# old_control_board.net
KiCad netlist of a schematic drawn in EAGLE
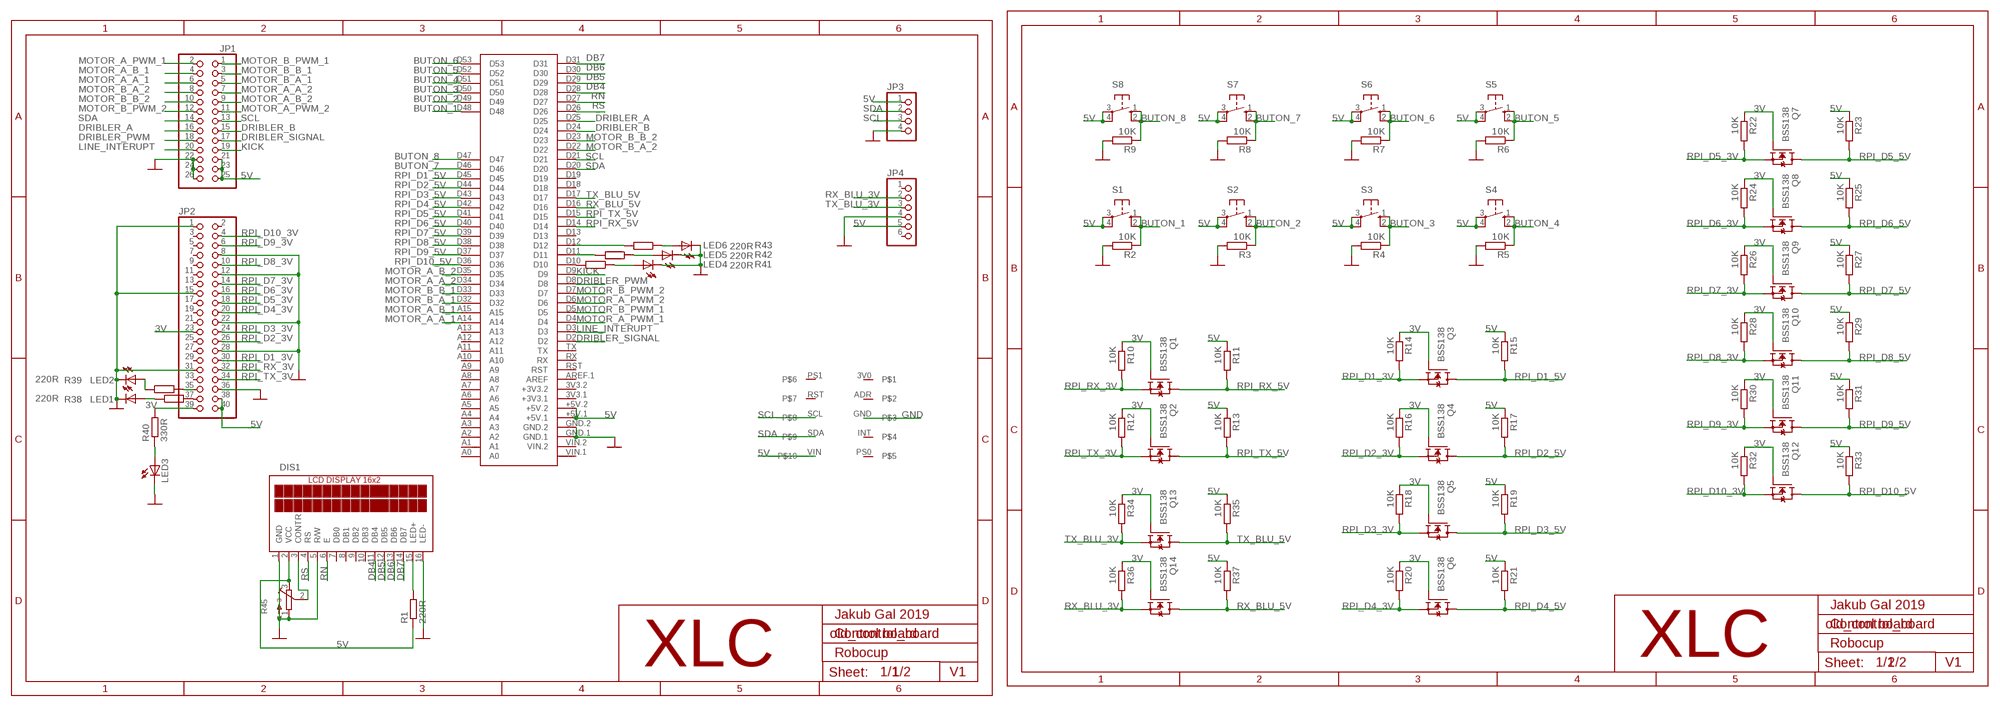
[diagram p0: schematic, sheet 1]

(export (version "E")
  (design (tool "Eeschema 10.0.6"))
  (components
    (comp (ref "DIS1")
      (value "LCD_DISPLEJ_16X2Z")
      (footprint "eagle-import:LCD_DISPLEJ_16X2")
      (libsource (lib "eagle-import") (part "LCD_DISPLEJ_16X2Z"))
    )
    (comp (ref "JP1")
      (value "PINHD-2X13_2.54")
      (footprint "eagle-import:2X13")
      (libsource (lib "eagle-import") (part "PINHD-2X13_2.54"))
    )
    (comp (ref "JP2")
      (value "PINHD-2X20_2.54")
      (footprint "eagle-import:2X20")
      (libsource (lib "eagle-import") (part "PINHD-2X20_2.54"))
    )
    (comp (ref "JP3")
      (value "PINHD-1X4_2.54")
      (footprint "eagle-import:1X04")
      (libsource (lib "eagle-import") (part "PINHD-1X4_2.54"))
    )
    (comp (ref "JP4")
      (value "PINHD-1X6_2.54")
      (footprint "eagle-import:1X06")
      (libsource (lib "eagle-import") (part "PINHD-1X6_2.54"))
    )
    (comp (ref "LED1")
      (value "LEDCHIPLED_0603")
      (footprint "eagle-import:CHIPLED_0603")
      (libsource (lib "eagle-import") (part "LEDCHIPLED_0603"))
    )
    (comp (ref "LED2")
      (value "LEDCHIPLED_0603")
      (footprint "eagle-import:CHIPLED_0603")
      (libsource (lib "eagle-import") (part "LEDCHIPLED_0603"))
    )
    (comp (ref "LED3")
      (value "LEDCHIPLED_0603")
      (footprint "eagle-import:CHIPLED_0603")
      (libsource (lib "eagle-import") (part "LEDCHIPLED_0603"))
    )
    (comp (ref "LED4")
      (value "LEDCHIPLED_0603")
      (footprint "eagle-import:CHIPLED_0603")
      (libsource (lib "eagle-import") (part "LEDCHIPLED_0603"))
    )
    (comp (ref "LED5")
      (value "LEDCHIPLED_0603")
      (footprint "eagle-import:CHIPLED_0603")
      (libsource (lib "eagle-import") (part "LEDCHIPLED_0603"))
    )
    (comp (ref "LED6")
      (value "LEDCHIPLED_0603")
      (footprint "eagle-import:CHIPLED_0603")
      (libsource (lib "eagle-import") (part "LEDCHIPLED_0603"))
    )
    (comp (ref "Q1")
      (value "BSS138")
      (footprint "eagle-import:SOT23")
      (fields (field (name "MF") "Fairchild"))
      (libsource (lib "eagle-import") (part "BSS138"))
    )
    (comp (ref "Q2")
      (value "BSS138")
      (footprint "eagle-import:SOT23")
      (fields (field (name "MF") "Fairchild"))
      (libsource (lib "eagle-import") (part "BSS138"))
    )
    (comp (ref "Q3")
      (value "BSS138")
      (footprint "eagle-import:SOT23")
      (fields (field (name "MF") "Fairchild"))
      (libsource (lib "eagle-import") (part "BSS138"))
    )
    (comp (ref "Q4")
      (value "BSS138")
      (footprint "eagle-import:SOT23")
      (fields (field (name "MF") "Fairchild"))
      (libsource (lib "eagle-import") (part "BSS138"))
    )
    (comp (ref "Q5")
      (value "BSS138")
      (footprint "eagle-import:SOT23")
      (fields (field (name "MF") "Fairchild"))
      (libsource (lib "eagle-import") (part "BSS138"))
    )
    (comp (ref "Q6")
      (value "BSS138")
      (footprint "eagle-import:SOT23")
      (fields (field (name "MF") "Fairchild"))
      (libsource (lib "eagle-import") (part "BSS138"))
    )
    (comp (ref "Q7")
      (value "BSS138")
      (footprint "eagle-import:SOT23")
      (fields (field (name "MF") "Fairchild"))
      (libsource (lib "eagle-import") (part "BSS138"))
    )
    (comp (ref "Q8")
      (value "BSS138")
      (footprint "eagle-import:SOT23")
      (fields (field (name "MF") "Fairchild"))
      (libsource (lib "eagle-import") (part "BSS138"))
    )
    (comp (ref "Q9")
      (value "BSS138")
      (footprint "eagle-import:SOT23")
      (fields (field (name "MF") "Fairchild"))
      (libsource (lib "eagle-import") (part "BSS138"))
    )
    (comp (ref "Q10")
      (value "BSS138")
      (footprint "eagle-import:SOT23")
      (fields (field (name "MF") "Fairchild"))
      (libsource (lib "eagle-import") (part "BSS138"))
    )
    (comp (ref "Q11")
      (value "BSS138")
      (footprint "eagle-import:SOT23")
      (fields (field (name "MF") "Fairchild"))
      (libsource (lib "eagle-import") (part "BSS138"))
    )
    (comp (ref "Q12")
      (value "BSS138")
      (footprint "eagle-import:SOT23")
      (fields (field (name "MF") "Fairchild"))
      (libsource (lib "eagle-import") (part "BSS138"))
    )
    (comp (ref "Q13")
      (value "BSS138")
      (footprint "eagle-import:SOT23")
      (fields (field (name "MF") "Fairchild"))
      (libsource (lib "eagle-import") (part "BSS138"))
    )
    (comp (ref "Q14")
      (value "BSS138")
      (footprint "eagle-import:SOT23")
      (fields (field (name "MF") "Fairchild"))
      (libsource (lib "eagle-import") (part "BSS138"))
    )
    (comp (ref "R1")
      (value "220R")
      (footprint "eagle-import:R0603")
      (libsource (lib "eagle-import") (part "R-EU_R0603"))
    )
    (comp (ref "R2")
      (value "10K")
      (footprint "eagle-import:R0603")
      (libsource (lib "eagle-import") (part "R-EU_R0603"))
    )
    (comp (ref "R3")
      (value "10K")
      (footprint "eagle-import:R0603")
      (libsource (lib "eagle-import") (part "R-EU_R0603"))
    )
    (comp (ref "R4")
      (value "10K")
      (footprint "eagle-import:R0603")
      (libsource (lib "eagle-import") (part "R-EU_R0603"))
    )
    (comp (ref "R5")
      (value "10K")
      (footprint "eagle-import:R0603")
      (libsource (lib "eagle-import") (part "R-EU_R0603"))
    )
    (comp (ref "R6")
      (value "10K")
      (footprint "eagle-import:R0603")
      (libsource (lib "eagle-import") (part "R-EU_R0603"))
    )
    (comp (ref "R7")
      (value "10K")
      (footprint "eagle-import:R0603")
      (libsource (lib "eagle-import") (part "R-EU_R0603"))
    )
    (comp (ref "R8")
      (value "10K")
      (footprint "eagle-import:R0603")
      (libsource (lib "eagle-import") (part "R-EU_R0603"))
    )
    (comp (ref "R9")
      (value "10K")
      (footprint "eagle-import:R0603")
      (libsource (lib "eagle-import") (part "R-EU_R0603"))
    )
    (comp (ref "R10")
      (value "10K")
      (footprint "eagle-import:R0603")
      (libsource (lib "eagle-import") (part "R-EU_R0603"))
    )
    (comp (ref "R11")
      (value "10K")
      (footprint "eagle-import:R0603")
      (libsource (lib "eagle-import") (part "R-EU_R0603"))
    )
    (comp (ref "R12")
      (value "10K")
      (footprint "eagle-import:R0603")
      (libsource (lib "eagle-import") (part "R-EU_R0603"))
    )
    (comp (ref "R13")
      (value "10K")
      (footprint "eagle-import:R0603")
      (libsource (lib "eagle-import") (part "R-EU_R0603"))
    )
    (comp (ref "R14")
      (value "10K")
      (footprint "eagle-import:R0603")
      (libsource (lib "eagle-import") (part "R-EU_R0603"))
    )
    (comp (ref "R15")
      (value "10K")
      (footprint "eagle-import:R0603")
      (libsource (lib "eagle-import") (part "R-EU_R0603"))
    )
    (comp (ref "R16")
      (value "10K")
      (footprint "eagle-import:R0603")
      (libsource (lib "eagle-import") (part "R-EU_R0603"))
    )
    (comp (ref "R17")
      (value "10K")
      (footprint "eagle-import:R0603")
      (libsource (lib "eagle-import") (part "R-EU_R0603"))
    )
    (comp (ref "R18")
      (value "10K")
      (footprint "eagle-import:R0603")
      (libsource (lib "eagle-import") (part "R-EU_R0603"))
    )
    (comp (ref "R19")
      (value "10K")
      (footprint "eagle-import:R0603")
      (libsource (lib "eagle-import") (part "R-EU_R0603"))
    )
    (comp (ref "R20")
      (value "10K")
      (footprint "eagle-import:R0603")
      (libsource (lib "eagle-import") (part "R-EU_R0603"))
    )
    (comp (ref "R21")
      (value "10K")
      (footprint "eagle-import:R0603")
      (libsource (lib "eagle-import") (part "R-EU_R0603"))
    )
    (comp (ref "R22")
      (value "10K")
      (footprint "eagle-import:R0603")
      (libsource (lib "eagle-import") (part "R-EU_R0603"))
    )
    (comp (ref "R23")
      (value "10K")
      (footprint "eagle-import:R0603")
      (libsource (lib "eagle-import") (part "R-EU_R0603"))
    )
    (comp (ref "R24")
      (value "10K")
      (footprint "eagle-import:R0603")
      (libsource (lib "eagle-import") (part "R-EU_R0603"))
    )
    (comp (ref "R25")
      (value "10K")
      (footprint "eagle-import:R0603")
      (libsource (lib "eagle-import") (part "R-EU_R0603"))
    )
    (comp (ref "R26")
      (value "10K")
      (footprint "eagle-import:R0603")
      (libsource (lib "eagle-import") (part "R-EU_R0603"))
    )
    (comp (ref "R27")
      (value "10K")
      (footprint "eagle-import:R0603")
      (libsource (lib "eagle-import") (part "R-EU_R0603"))
    )
    (comp (ref "R28")
      (value "10K")
      (footprint "eagle-import:R0603")
      (libsource (lib "eagle-import") (part "R-EU_R0603"))
    )
    (comp (ref "R29")
      (value "10K")
      (footprint "eagle-import:R0603")
      (libsource (lib "eagle-import") (part "R-EU_R0603"))
    )
    (comp (ref "R30")
      (value "10K")
      (footprint "eagle-import:R0603")
      (libsource (lib "eagle-import") (part "R-EU_R0603"))
    )
    (comp (ref "R31")
      (value "10K")
      (footprint "eagle-import:R0603")
      (libsource (lib "eagle-import") (part "R-EU_R0603"))
    )
    (comp (ref "R32")
      (value "10K")
      (footprint "eagle-import:R0603")
      (libsource (lib "eagle-import") (part "R-EU_R0603"))
    )
    (comp (ref "R33")
      (value "10K")
      (footprint "eagle-import:R0603")
      (libsource (lib "eagle-import") (part "R-EU_R0603"))
    )
    (comp (ref "R34")
      (value "10K")
      (footprint "eagle-import:R0603")
      (libsource (lib "eagle-import") (part "R-EU_R0603"))
    )
    (comp (ref "R35")
      (value "10K")
      (footprint "eagle-import:R0603")
      (libsource (lib "eagle-import") (part "R-EU_R0603"))
    )
    (comp (ref "R36")
      (value "10K")
      (footprint "eagle-import:R0603")
      (libsource (lib "eagle-import") (part "R-EU_R0603"))
    )
    (comp (ref "R37")
      (value "10K")
      (footprint "eagle-import:R0603")
      (libsource (lib "eagle-import") (part "R-EU_R0603"))
    )
    (comp (ref "R38")
      (value "220R")
      (footprint "eagle-import:R0603")
      (libsource (lib "eagle-import") (part "R-EU_R0603"))
    )
    (comp (ref "R39")
      (value "220R")
      (footprint "eagle-import:R0603")
      (libsource (lib "eagle-import") (part "R-EU_R0603"))
    )
    (comp (ref "R40")
      (value "330R")
      (footprint "eagle-import:R0603")
      (libsource (lib "eagle-import") (part "R-EU_R0603"))
    )
    (comp (ref "R41")
      (value "220R")
      (footprint "eagle-import:R0603")
      (libsource (lib "eagle-import") (part "R-EU_R0603"))
    )
    (comp (ref "R42")
      (value "220R")
      (footprint "eagle-import:R0603")
      (libsource (lib "eagle-import") (part "R-EU_R0603"))
    )
    (comp (ref "R43")
      (value "220R")
      (footprint "eagle-import:R0603")
      (libsource (lib "eagle-import") (part "R-EU_R0603"))
    )
    (comp (ref "R45")
      (value "3362P")
      (footprint "eagle-import:3362P")
      (libsource (lib "eagle-import") (part "3362P"))
    )
    (comp (ref "S1")
      (value "10-XX")
      (footprint "eagle-import:B3F-10XX")
      (fields (field (name "MPN") "B3F-1000"))
      (libsource (lib "eagle-import") (part "10-XX"))
    )
    (comp (ref "S2")
      (value "10-XX")
      (footprint "eagle-import:B3F-10XX")
      (fields (field (name "MPN") "B3F-1000"))
      (libsource (lib "eagle-import") (part "10-XX"))
    )
    (comp (ref "S3")
      (value "10-XX")
      (footprint "eagle-import:B3F-10XX")
      (fields (field (name "MPN") "B3F-1000"))
      (libsource (lib "eagle-import") (part "10-XX"))
    )
    (comp (ref "S4")
      (value "10-XX")
      (footprint "eagle-import:B3F-10XX")
      (fields (field (name "MPN") "B3F-1000"))
      (libsource (lib "eagle-import") (part "10-XX"))
    )
    (comp (ref "S5")
      (value "10-XX")
      (footprint "eagle-import:B3F-10XX")
      (fields (field (name "MPN") "B3F-1000"))
      (libsource (lib "eagle-import") (part "10-XX"))
    )
    (comp (ref "S6")
      (value "10-XX")
      (footprint "eagle-import:B3F-10XX")
      (fields (field (name "MPN") "B3F-1000"))
      (libsource (lib "eagle-import") (part "10-XX"))
    )
    (comp (ref "S7")
      (value "10-XX")
      (footprint "eagle-import:B3F-10XX")
      (fields (field (name "MPN") "B3F-1000"))
      (libsource (lib "eagle-import") (part "10-XX"))
    )
    (comp (ref "S8")
      (value "10-XX")
      (footprint "eagle-import:B3F-10XX")
      (fields (field (name "MPN") "B3F-1000"))
      (libsource (lib "eagle-import") (part "10-XX"))
    )
    (comp (ref "U$1")
      (value "MEGA2560_MIKRO")
      (footprint "eagle-import:MEGA2560_MIKRO")
      (libsource (lib "eagle-import") (part "MEGA2560_MIKRO"))
    )
    (comp (ref "U$2")
      (value "BNO055")
      (footprint "eagle-import:BNO005")
      (libsource (lib "eagle-import") (part "BNO055"))
    )
  )
  (nets
    (net (code "1") (name "/3V") (class "Default")
      (node (ref "JP2") (pin "23") (pinfunction "23_23") (pintype "passive"))
      (node (ref "JP2") (pin "39") (pinfunction "39_39") (pintype "passive"))
      (node (ref "Q1") (pin "1") (pinfunction "G_1") (pintype "passive"))
      (node (ref "Q10") (pin "1") (pinfunction "G_1") (pintype "passive"))
      (node (ref "Q11") (pin "1") (pinfunction "G_1") (pintype "passive"))
      (node (ref "Q12") (pin "1") (pinfunction "G_1") (pintype "passive"))
      (node (ref "Q13") (pin "1") (pinfunction "G_1") (pintype "passive"))
      (node (ref "Q14") (pin "1") (pinfunction "G_1") (pintype "passive"))
      (node (ref "Q2") (pin "1") (pinfunction "G_1") (pintype "passive"))
      (node (ref "Q3") (pin "1") (pinfunction "G_1") (pintype "passive"))
      (node (ref "Q4") (pin "1") (pinfunction "G_1") (pintype "passive"))
      (node (ref "Q5") (pin "1") (pinfunction "G_1") (pintype "passive"))
      (node (ref "Q6") (pin "1") (pinfunction "G_1") (pintype "passive"))
      (node (ref "Q7") (pin "1") (pinfunction "G_1") (pintype "passive"))
      (node (ref "Q8") (pin "1") (pinfunction "G_1") (pintype "passive"))
      (node (ref "Q9") (pin "1") (pinfunction "G_1") (pintype "passive"))
      (node (ref "R10") (pin "1") (pinfunction "1_1") (pintype "passive"))
      (node (ref "R12") (pin "1") (pinfunction "1_1") (pintype "passive"))
      (node (ref "R14") (pin "1") (pinfunction "1_1") (pintype "passive"))
      (node (ref "R16") (pin "1") (pinfunction "1_1") (pintype "passive"))
      (node (ref "R18") (pin "1") (pinfunction "1_1") (pintype "passive"))
      (node (ref "R20") (pin "1") (pinfunction "1_1") (pintype "passive"))
      (node (ref "R22") (pin "1") (pinfunction "1_1") (pintype "passive"))
      (node (ref "R24") (pin "1") (pinfunction "1_1") (pintype "passive"))
      (node (ref "R26") (pin "1") (pinfunction "1_1") (pintype "passive"))
      (node (ref "R28") (pin "1") (pinfunction "1_1") (pintype "passive"))
      (node (ref "R30") (pin "1") (pinfunction "1_1") (pintype "passive"))
      (node (ref "R32") (pin "1") (pinfunction "1_1") (pintype "passive"))
      (node (ref "R34") (pin "1") (pinfunction "1_1") (pintype "passive"))
      (node (ref "R36") (pin "1") (pinfunction "1_1") (pintype "passive"))
      (node (ref "R40") (pin "2") (pinfunction "2_2") (pintype "passive"))
    )
    (net (code "2") (name "/5V") (class "Default")
      (node (ref "DIS1") (pin "2") (pinfunction "VCC_2") (pintype "power_in"))
      (node (ref "JP1") (pin "21") (pinfunction "21_21") (pintype "passive"))
      (node (ref "JP1") (pin "23") (pinfunction "23_23") (pintype "passive"))
      (node (ref "JP1") (pin "25") (pinfunction "25_25") (pintype "passive"))
      (node (ref "JP2") (pin "38") (pinfunction "38_38") (pintype "passive"))
      (node (ref "JP2") (pin "40") (pinfunction "40_40") (pintype "passive"))
      (node (ref "JP3") (pin "1") (pinfunction "1_1") (pintype "passive"))
      (node (ref "JP4") (pin "5") (pinfunction "5_5") (pintype "passive"))
      (node (ref "R1") (pin "1") (pinfunction "1_1") (pintype "passive"))
      (node (ref "R11") (pin "1") (pinfunction "1_1") (pintype "passive"))
      (node (ref "R13") (pin "1") (pinfunction "1_1") (pintype "passive"))
      (node (ref "R15") (pin "1") (pinfunction "1_1") (pintype "passive"))
      (node (ref "R17") (pin "1") (pinfunction "1_1") (pintype "passive"))
      (node (ref "R19") (pin "1") (pinfunction "1_1") (pintype "passive"))
      (node (ref "R21") (pin "1") (pinfunction "1_1") (pintype "passive"))
      (node (ref "R23") (pin "1") (pinfunction "1_1") (pintype "passive"))
      (node (ref "R25") (pin "1") (pinfunction "1_1") (pintype "passive"))
      (node (ref "R27") (pin "1") (pinfunction "1_1") (pintype "passive"))
      (node (ref "R29") (pin "1") (pinfunction "1_1") (pintype "passive"))
      (node (ref "R31") (pin "1") (pinfunction "1_1") (pintype "passive"))
      (node (ref "R33") (pin "1") (pinfunction "1_1") (pintype "passive"))
      (node (ref "R35") (pin "1") (pinfunction "1_1") (pintype "passive"))
      (node (ref "R37") (pin "1") (pinfunction "1_1") (pintype "passive"))
      (node (ref "R45") (pin "3") (pinfunction "3_3") (pintype "passive"))
      (node (ref "S1") (pin "3") (pinfunction "P_3") (pintype "passive"))
      (node (ref "S1") (pin "4") (pinfunction "P1_4") (pintype "passive"))
      (node (ref "S2") (pin "3") (pinfunction "P_3") (pintype "passive"))
      (node (ref "S2") (pin "4") (pinfunction "P1_4") (pintype "passive"))
      (node (ref "S3") (pin "3") (pinfunction "P_3") (pintype "passive"))
      (node (ref "S3") (pin "4") (pinfunction "P1_4") (pintype "passive"))
      (node (ref "S4") (pin "3") (pinfunction "P_3") (pintype "passive"))
      (node (ref "S4") (pin "4") (pinfunction "P1_4") (pintype "passive"))
      (node (ref "S5") (pin "3") (pinfunction "P_3") (pintype "passive"))
      (node (ref "S5") (pin "4") (pinfunction "P1_4") (pintype "passive"))
      (node (ref "S6") (pin "3") (pinfunction "P_3") (pintype "passive"))
      (node (ref "S6") (pin "4") (pinfunction "P1_4") (pintype "passive"))
      (node (ref "S7") (pin "3") (pinfunction "P_3") (pintype "passive"))
      (node (ref "S7") (pin "4") (pinfunction "P1_4") (pintype "passive"))
      (node (ref "S8") (pin "3") (pinfunction "P_3") (pintype "passive"))
      (node (ref "S8") (pin "4") (pinfunction "P1_4") (pintype "passive"))
      (node (ref "U$1") (pin "+5V.1") (pinfunction "+5V.1_+5V.1") (pintype "bidirectional"))
      (node (ref "U$1") (pin "+5V.2") (pinfunction "+5V.2_+5V.2") (pintype "bidirectional"))
      (node (ref "U$2") (pin "VIN") (pinfunction "P$10_VIN") (pintype "bidirectional"))
    )
    (net (code "3") (name "/BUTON_1") (class "Default")
      (node (ref "R2") (pin "1") (pinfunction "1_1") (pintype "passive"))
      (node (ref "S1") (pin "1") (pinfunction "S_1") (pintype "passive"))
      (node (ref "S1") (pin "2") (pinfunction "S1_2") (pintype "passive"))
      (node (ref "U$1") (pin "D48") (pinfunction "D48_D48") (pintype "bidirectional"))
    )
    (net (code "4") (name "/BUTON_2") (class "Default")
      (node (ref "R3") (pin "1") (pinfunction "1_1") (pintype "passive"))
      (node (ref "S2") (pin "1") (pinfunction "S_1") (pintype "passive"))
      (node (ref "S2") (pin "2") (pinfunction "S1_2") (pintype "passive"))
      (node (ref "U$1") (pin "D49") (pinfunction "D49_D49") (pintype "bidirectional"))
    )
    (net (code "5") (name "/BUTON_3") (class "Default")
      (node (ref "R4") (pin "1") (pinfunction "1_1") (pintype "passive"))
      (node (ref "S3") (pin "1") (pinfunction "S_1") (pintype "passive"))
      (node (ref "S3") (pin "2") (pinfunction "S1_2") (pintype "passive"))
      (node (ref "U$1") (pin "D50") (pinfunction "D50_D50") (pintype "bidirectional"))
    )
    (net (code "6") (name "/BUTON_4") (class "Default")
      (node (ref "R5") (pin "1") (pinfunction "1_1") (pintype "passive"))
      (node (ref "S4") (pin "1") (pinfunction "S_1") (pintype "passive"))
      (node (ref "S4") (pin "2") (pinfunction "S1_2") (pintype "passive"))
      (node (ref "U$1") (pin "D51") (pinfunction "D51_D51") (pintype "bidirectional"))
    )
    (net (code "7") (name "/BUTON_5") (class "Default")
      (node (ref "R6") (pin "1") (pinfunction "1_1") (pintype "passive"))
      (node (ref "S5") (pin "1") (pinfunction "S_1") (pintype "passive"))
      (node (ref "S5") (pin "2") (pinfunction "S1_2") (pintype "passive"))
      (node (ref "U$1") (pin "D52") (pinfunction "D52_D52") (pintype "bidirectional"))
    )
    (net (code "8") (name "/BUTON_6") (class "Default")
      (node (ref "R7") (pin "1") (pinfunction "1_1") (pintype "passive"))
      (node (ref "S6") (pin "1") (pinfunction "S_1") (pintype "passive"))
      (node (ref "S6") (pin "2") (pinfunction "S1_2") (pintype "passive"))
      (node (ref "U$1") (pin "D53") (pinfunction "D53_D53") (pintype "bidirectional"))
    )
    (net (code "9") (name "/BUTON_7") (class "Default")
      (node (ref "R8") (pin "1") (pinfunction "1_1") (pintype "passive"))
      (node (ref "S7") (pin "1") (pinfunction "S_1") (pintype "passive"))
      (node (ref "S7") (pin "2") (pinfunction "S1_2") (pintype "passive"))
      (node (ref "U$1") (pin "D46") (pinfunction "D46_D46") (pintype "bidirectional"))
    )
    (net (code "10") (name "/BUTON_8") (class "Default")
      (node (ref "R9") (pin "1") (pinfunction "1_1") (pintype "passive"))
      (node (ref "S8") (pin "1") (pinfunction "S_1") (pintype "passive"))
      (node (ref "S8") (pin "2") (pinfunction "S1_2") (pintype "passive"))
      (node (ref "U$1") (pin "D47") (pinfunction "D47_D47") (pintype "bidirectional"))
    )
    (net (code "11") (name "/DB4") (class "Default")
      (node (ref "DIS1") (pin "11") (pinfunction "DB4_11") (pintype "bidirectional"))
      (node (ref "U$1") (pin "D28") (pinfunction "D28_D28") (pintype "bidirectional"))
    )
    (net (code "12") (name "/DB5") (class "Default")
      (node (ref "DIS1") (pin "12") (pinfunction "DB5_12") (pintype "bidirectional"))
      (node (ref "U$1") (pin "D29") (pinfunction "D29_D29") (pintype "bidirectional"))
    )
    (net (code "13") (name "/DB6") (class "Default")
      (node (ref "DIS1") (pin "13") (pinfunction "DB6_13") (pintype "bidirectional"))
      (node (ref "U$1") (pin "D30") (pinfunction "D30_D30") (pintype "bidirectional"))
    )
    (net (code "14") (name "/DB7") (class "Default")
      (node (ref "DIS1") (pin "14") (pinfunction "DB7_14") (pintype "bidirectional"))
      (node (ref "U$1") (pin "D31") (pinfunction "D31_D31") (pintype "bidirectional"))
    )
    (net (code "15") (name "/DRIBLER_A") (class "Default")
      (node (ref "JP1") (pin "16") (pinfunction "16_16") (pintype "passive"))
      (node (ref "U$1") (pin "D25") (pinfunction "D25_D25") (pintype "bidirectional"))
    )
    (net (code "16") (name "/DRIBLER_B") (class "Default")
      (node (ref "JP1") (pin "15") (pinfunction "15_15") (pintype "passive"))
      (node (ref "U$1") (pin "D24") (pinfunction "D24_D24") (pintype "bidirectional"))
    )
    (net (code "17") (name "/DRIBLER_PWM") (class "Default")
      (node (ref "JP1") (pin "18") (pinfunction "18_18") (pintype "passive"))
      (node (ref "U$1") (pin "D8") (pinfunction "D8_D8") (pintype "bidirectional"))
    )
    (net (code "18") (name "/DRIBLER_SIGNAL") (class "Default")
      (node (ref "JP1") (pin "17") (pinfunction "17_17") (pintype "passive"))
      (node (ref "U$1") (pin "D2") (pinfunction "D2_D2") (pintype "bidirectional"))
    )
    (net (code "19") (name "/KICK") (class "Default")
      (node (ref "JP1") (pin "19") (pinfunction "19_19") (pintype "passive"))
      (node (ref "U$1") (pin "D9") (pinfunction "D9_D9") (pintype "bidirectional"))
    )
    (net (code "20") (name "/LINE_INTERUPT") (class "Default")
      (node (ref "JP1") (pin "20") (pinfunction "20_20") (pintype "passive"))
      (node (ref "U$1") (pin "D3") (pinfunction "D3_D3") (pintype "bidirectional"))
    )
    (net (code "21") (name "/MOTOR_A_A_1") (class "Default")
      (node (ref "JP1") (pin "6") (pinfunction "6_6") (pintype "passive"))
      (node (ref "U$1") (pin "A14") (pinfunction "A14_A14") (pintype "bidirectional"))
    )
    (net (code "22") (name "/MOTOR_A_A_2") (class "Default")
      (node (ref "JP1") (pin "7") (pinfunction "7_7") (pintype "passive"))
      (node (ref "U$1") (pin "D34") (pinfunction "D34_D34") (pintype "bidirectional"))
    )
    (net (code "23") (name "/MOTOR_A_B_1") (class "Default")
      (node (ref "JP1") (pin "4") (pinfunction "4_4") (pintype "passive"))
      (node (ref "U$1") (pin "A15") (pinfunction "A15_A15") (pintype "bidirectional"))
    )
    (net (code "24") (name "/MOTOR_A_B_2") (class "Default")
      (node (ref "JP1") (pin "9") (pinfunction "9_9") (pintype "passive"))
      (node (ref "U$1") (pin "D35") (pinfunction "D35_D35") (pintype "bidirectional"))
    )
    (net (code "25") (name "/MOTOR_A_PWM_1") (class "Default")
      (node (ref "JP1") (pin "2") (pinfunction "2_2") (pintype "passive"))
      (node (ref "U$1") (pin "D4") (pinfunction "D4_D4") (pintype "bidirectional"))
    )
    (net (code "26") (name "/MOTOR_A_PWM_2") (class "Default")
      (node (ref "JP1") (pin "11") (pinfunction "11_11") (pintype "passive"))
      (node (ref "U$1") (pin "D6") (pinfunction "D6_D6") (pintype "bidirectional"))
    )
    (net (code "27") (name "/MOTOR_B_A_1") (class "Default")
      (node (ref "JP1") (pin "5") (pinfunction "5_5") (pintype "passive"))
      (node (ref "U$1") (pin "D32") (pinfunction "D32_D32") (pintype "bidirectional"))
    )
    (net (code "28") (name "/MOTOR_B_A_2") (class "Default")
      (node (ref "JP1") (pin "8") (pinfunction "8_8") (pintype "passive"))
      (node (ref "U$1") (pin "D22") (pinfunction "D22_D22") (pintype "bidirectional"))
    )
    (net (code "29") (name "/MOTOR_B_B_1") (class "Default")
      (node (ref "JP1") (pin "3") (pinfunction "3_3") (pintype "passive"))
      (node (ref "U$1") (pin "D33") (pinfunction "D33_D33") (pintype "bidirectional"))
    )
    (net (code "30") (name "/MOTOR_B_B_2") (class "Default")
      (node (ref "JP1") (pin "10") (pinfunction "10_10") (pintype "passive"))
      (node (ref "U$1") (pin "D23") (pinfunction "D23_D23") (pintype "bidirectional"))
    )
    (net (code "31") (name "/MOTOR_B_PWM_1") (class "Default")
      (node (ref "JP1") (pin "1") (pinfunction "1_1") (pintype "passive"))
      (node (ref "U$1") (pin "D5") (pinfunction "D5_D5") (pintype "bidirectional"))
    )
    (net (code "32") (name "/MOTOR_B_PWM_2") (class "Default")
      (node (ref "JP1") (pin "12") (pinfunction "12_12") (pintype "passive"))
      (node (ref "U$1") (pin "D7") (pinfunction "D7_D7") (pintype "bidirectional"))
    )
    (net (code "33") (name "/RN") (class "Default")
      (node (ref "DIS1") (pin "6") (pinfunction "E_6") (pintype "input"))
      (node (ref "U$1") (pin "D27") (pinfunction "D27_D27") (pintype "bidirectional"))
    )
    (net (code "34") (name "/RPI_D1_3V") (class "Default")
      (node (ref "JP2") (pin "30") (pinfunction "30_30") (pintype "passive"))
      (node (ref "Q3") (pin "2") (pinfunction "S_2") (pintype "passive"))
      (node (ref "R14") (pin "2") (pinfunction "2_2") (pintype "passive"))
    )
    (net (code "35") (name "/RPI_D1_5V") (class "Default")
      (node (ref "Q3") (pin "3") (pinfunction "D_3") (pintype "passive"))
      (node (ref "R15") (pin "2") (pinfunction "2_2") (pintype "passive"))
      (node (ref "U$1") (pin "D45") (pinfunction "D45_D45") (pintype "bidirectional"))
    )
    (net (code "36") (name "/RPI_D2_3V") (class "Default")
      (node (ref "JP2") (pin "26") (pinfunction "26_26") (pintype "passive"))
      (node (ref "Q4") (pin "2") (pinfunction "S_2") (pintype "passive"))
      (node (ref "R16") (pin "2") (pinfunction "2_2") (pintype "passive"))
    )
    (net (code "37") (name "/RPI_D2_5V") (class "Default")
      (node (ref "Q4") (pin "3") (pinfunction "D_3") (pintype "passive"))
      (node (ref "R17") (pin "2") (pinfunction "2_2") (pintype "passive"))
      (node (ref "U$1") (pin "D44") (pinfunction "D44_D44") (pintype "bidirectional"))
    )
    (net (code "38") (name "/RPI_D3_3V") (class "Default")
      (node (ref "JP2") (pin "24") (pinfunction "24_24") (pintype "passive"))
      (node (ref "Q5") (pin "2") (pinfunction "S_2") (pintype "passive"))
      (node (ref "R18") (pin "2") (pinfunction "2_2") (pintype "passive"))
    )
    (net (code "39") (name "/RPI_D3_5V") (class "Default")
      (node (ref "Q5") (pin "3") (pinfunction "D_3") (pintype "passive"))
      (node (ref "R19") (pin "2") (pinfunction "2_2") (pintype "passive"))
      (node (ref "U$1") (pin "D43") (pinfunction "D43_D43") (pintype "bidirectional"))
    )
    (net (code "40") (name "/RPI_D4_3V") (class "Default")
      (node (ref "JP2") (pin "20") (pinfunction "20_20") (pintype "passive"))
      (node (ref "Q6") (pin "2") (pinfunction "S_2") (pintype "passive"))
      (node (ref "R20") (pin "2") (pinfunction "2_2") (pintype "passive"))
    )
    (net (code "41") (name "/RPI_D4_5V") (class "Default")
      (node (ref "Q6") (pin "3") (pinfunction "D_3") (pintype "passive"))
      (node (ref "R21") (pin "2") (pinfunction "2_2") (pintype "passive"))
      (node (ref "U$1") (pin "D42") (pinfunction "D42_D42") (pintype "bidirectional"))
    )
    (net (code "42") (name "/RPI_D5_3V") (class "Default")
      (node (ref "JP2") (pin "18") (pinfunction "18_18") (pintype "passive"))
      (node (ref "Q7") (pin "2") (pinfunction "S_2") (pintype "passive"))
      (node (ref "R22") (pin "2") (pinfunction "2_2") (pintype "passive"))
    )
    (net (code "43") (name "/RPI_D5_5V") (class "Default")
      (node (ref "Q7") (pin "3") (pinfunction "D_3") (pintype "passive"))
      (node (ref "R23") (pin "2") (pinfunction "2_2") (pintype "passive"))
      (node (ref "U$1") (pin "D41") (pinfunction "D41_D41") (pintype "bidirectional"))
    )
    (net (code "44") (name "/RPI_D6_3V") (class "Default")
      (node (ref "JP2") (pin "16") (pinfunction "16_16") (pintype "passive"))
      (node (ref "Q8") (pin "2") (pinfunction "S_2") (pintype "passive"))
      (node (ref "R24") (pin "2") (pinfunction "2_2") (pintype "passive"))
    )
    (net (code "45") (name "/RPI_D6_5V") (class "Default")
      (node (ref "Q8") (pin "3") (pinfunction "D_3") (pintype "passive"))
      (node (ref "R25") (pin "2") (pinfunction "2_2") (pintype "passive"))
      (node (ref "U$1") (pin "D40") (pinfunction "D40_D40") (pintype "bidirectional"))
    )
    (net (code "46") (name "/RPI_D7_3V") (class "Default")
      (node (ref "JP2") (pin "14") (pinfunction "14_14") (pintype "passive"))
      (node (ref "Q9") (pin "2") (pinfunction "S_2") (pintype "passive"))
      (node (ref "R26") (pin "2") (pinfunction "2_2") (pintype "passive"))
    )
    (net (code "47") (name "/RPI_D7_5V") (class "Default")
      (node (ref "Q9") (pin "3") (pinfunction "D_3") (pintype "passive"))
      (node (ref "R27") (pin "2") (pinfunction "2_2") (pintype "passive"))
      (node (ref "U$1") (pin "D39") (pinfunction "D39_D39") (pintype "bidirectional"))
    )
    (net (code "48") (name "/RPI_D8_3V") (class "Default")
      (node (ref "JP2") (pin "10") (pinfunction "10_10") (pintype "passive"))
      (node (ref "Q10") (pin "2") (pinfunction "S_2") (pintype "passive"))
      (node (ref "R28") (pin "2") (pinfunction "2_2") (pintype "passive"))
    )
    (net (code "49") (name "/RPI_D8_5V") (class "Default")
      (node (ref "Q10") (pin "3") (pinfunction "D_3") (pintype "passive"))
      (node (ref "R29") (pin "2") (pinfunction "2_2") (pintype "passive"))
      (node (ref "U$1") (pin "D38") (pinfunction "D38_D38") (pintype "bidirectional"))
    )
    (net (code "50") (name "/RPI_D9_3V") (class "Default")
      (node (ref "JP2") (pin "6") (pinfunction "6_6") (pintype "passive"))
      (node (ref "Q11") (pin "2") (pinfunction "S_2") (pintype "passive"))
      (node (ref "R30") (pin "2") (pinfunction "2_2") (pintype "passive"))
    )
    (net (code "51") (name "/RPI_D9_5V") (class "Default")
      (node (ref "Q11") (pin "3") (pinfunction "D_3") (pintype "passive"))
      (node (ref "R31") (pin "2") (pinfunction "2_2") (pintype "passive"))
      (node (ref "U$1") (pin "D37") (pinfunction "D37_D37") (pintype "bidirectional"))
    )
    (net (code "52") (name "/RPI_D10_3V") (class "Default")
      (node (ref "JP2") (pin "4") (pinfunction "4_4") (pintype "passive"))
      (node (ref "Q12") (pin "2") (pinfunction "S_2") (pintype "passive"))
      (node (ref "R32") (pin "2") (pinfunction "2_2") (pintype "passive"))
    )
    (net (code "53") (name "/RPI_D10_5V") (class "Default")
      (node (ref "Q12") (pin "3") (pinfunction "D_3") (pintype "passive"))
      (node (ref "R33") (pin "2") (pinfunction "2_2") (pintype "passive"))
      (node (ref "U$1") (pin "D36") (pinfunction "D36_D36") (pintype "bidirectional"))
    )
    (net (code "54") (name "/RPI_RX_3V") (class "Default")
      (node (ref "JP2") (pin "32") (pinfunction "32_32") (pintype "passive"))
      (node (ref "Q1") (pin "2") (pinfunction "S_2") (pintype "passive"))
      (node (ref "R10") (pin "2") (pinfunction "2_2") (pintype "passive"))
    )
    (net (code "55") (name "/RPI_RX_5V") (class "Default")
      (node (ref "Q1") (pin "3") (pinfunction "D_3") (pintype "passive"))
      (node (ref "R11") (pin "2") (pinfunction "2_2") (pintype "passive"))
      (node (ref "U$1") (pin "D14") (pinfunction "D14_D14") (pintype "bidirectional"))
    )
    (net (code "56") (name "/RPI_TX_3V") (class "Default")
      (node (ref "JP2") (pin "34") (pinfunction "34_34") (pintype "passive"))
      (node (ref "Q2") (pin "2") (pinfunction "S_2") (pintype "passive"))
      (node (ref "R12") (pin "2") (pinfunction "2_2") (pintype "passive"))
    )
    (net (code "57") (name "/RPI_TX_5V") (class "Default")
      (node (ref "Q2") (pin "3") (pinfunction "D_3") (pintype "passive"))
      (node (ref "R13") (pin "2") (pinfunction "2_2") (pintype "passive"))
      (node (ref "U$1") (pin "D15") (pinfunction "D15_D15") (pintype "bidirectional"))
    )
    (net (code "58") (name "/RS") (class "Default")
      (node (ref "DIS1") (pin "4") (pinfunction "RS_4") (pintype "input"))
      (node (ref "U$1") (pin "D26") (pinfunction "D26_D26") (pintype "bidirectional"))
    )
    (net (code "59") (name "/RX_BLU_3V") (class "Default")
      (node (ref "JP4") (pin "2") (pinfunction "2_2") (pintype "passive"))
      (node (ref "Q14") (pin "2") (pinfunction "S_2") (pintype "passive"))
      (node (ref "R36") (pin "2") (pinfunction "2_2") (pintype "passive"))
    )
    (net (code "60") (name "/RX_BLU_5V") (class "Default")
      (node (ref "Q14") (pin "3") (pinfunction "D_3") (pintype "passive"))
      (node (ref "R37") (pin "2") (pinfunction "2_2") (pintype "passive"))
      (node (ref "U$1") (pin "D16") (pinfunction "D16_D16") (pintype "bidirectional"))
    )
    (net (code "61") (name "/SCL") (class "Default")
      (node (ref "JP1") (pin "13") (pinfunction "13_13") (pintype "passive"))
      (node (ref "JP3") (pin "3") (pinfunction "3_3") (pintype "passive"))
      (node (ref "U$1") (pin "D21") (pinfunction "D21_D21") (pintype "bidirectional"))
      (node (ref "U$2") (pin "SCL") (pinfunction "P$8_SCL") (pintype "bidirectional"))
    )
    (net (code "62") (name "/SDA") (class "Default")
      (node (ref "JP1") (pin "14") (pinfunction "14_14") (pintype "passive"))
      (node (ref "JP3") (pin "2") (pinfunction "2_2") (pintype "passive"))
      (node (ref "U$1") (pin "D20") (pinfunction "D20_D20") (pintype "bidirectional"))
      (node (ref "U$2") (pin "SDA") (pinfunction "P$9_SDA") (pintype "bidirectional"))
    )
    (net (code "63") (name "/TX_BLU_3V") (class "Default")
      (node (ref "JP4") (pin "3") (pinfunction "3_3") (pintype "passive"))
      (node (ref "Q13") (pin "2") (pinfunction "S_2") (pintype "passive"))
      (node (ref "R34") (pin "2") (pinfunction "2_2") (pintype "passive"))
    )
    (net (code "64") (name "/TX_BLU_5V") (class "Default")
      (node (ref "Q13") (pin "3") (pinfunction "D_3") (pintype "passive"))
      (node (ref "R35") (pin "2") (pinfunction "2_2") (pintype "passive"))
      (node (ref "U$1") (pin "D17") (pinfunction "D17_D17") (pintype "bidirectional"))
    )
    (net (code "65") (name "GND") (class "Default")
      (node (ref "DIS1") (pin "1") (pinfunction "GND_1") (pintype "power_in"))
      (node (ref "DIS1") (pin "16") (pinfunction "LED-_16") (pintype "passive"))
      (node (ref "DIS1") (pin "5") (pinfunction "R/W_5") (pintype "input"))
      (node (ref "JP1") (pin "22") (pinfunction "22_22") (pintype "passive"))
      (node (ref "JP1") (pin "24") (pinfunction "24_24") (pintype "passive"))
      (node (ref "JP1") (pin "26") (pinfunction "26_26") (pintype "passive"))
      (node (ref "JP2") (pin "1") (pinfunction "1_1") (pintype "passive"))
      (node (ref "JP2") (pin "12") (pinfunction "12_12") (pintype "passive"))
      (node (ref "JP2") (pin "15") (pinfunction "15_15") (pintype "passive"))
      (node (ref "JP2") (pin "22") (pinfunction "22_22") (pintype "passive"))
      (node (ref "JP2") (pin "28") (pinfunction "28_28") (pintype "passive"))
      (node (ref "JP2") (pin "31") (pinfunction "31_31") (pintype "passive"))
      (node (ref "JP2") (pin "36") (pinfunction "36_36") (pintype "passive"))
      (node (ref "JP2") (pin "8") (pinfunction "8_8") (pintype "passive"))
      (node (ref "JP3") (pin "4") (pinfunction "4_4") (pintype "passive"))
      (node (ref "JP4") (pin "4") (pinfunction "4_4") (pintype "passive"))
      (node (ref "LED1") (pin "C") (pinfunction "C_C") (pintype "passive"))
      (node (ref "LED2") (pin "C") (pinfunction "C_C") (pintype "passive"))
      (node (ref "LED3") (pin "C") (pinfunction "C_C") (pintype "passive"))
      (node (ref "LED4") (pin "C") (pinfunction "C_C") (pintype "passive"))
      (node (ref "LED5") (pin "C") (pinfunction "C_C") (pintype "passive"))
      (node (ref "LED6") (pin "C") (pinfunction "C_C") (pintype "passive"))
      (node (ref "R2") (pin "2") (pinfunction "2_2") (pintype "passive"))
      (node (ref "R3") (pin "2") (pinfunction "2_2") (pintype "passive"))
      (node (ref "R4") (pin "2") (pinfunction "2_2") (pintype "passive"))
      (node (ref "R45") (pin "1") (pinfunction "1_1") (pintype "passive"))
      (node (ref "R5") (pin "2") (pinfunction "2_2") (pintype "passive"))
      (node (ref "R6") (pin "2") (pinfunction "2_2") (pintype "passive"))
      (node (ref "R7") (pin "2") (pinfunction "2_2") (pintype "passive"))
      (node (ref "R8") (pin "2") (pinfunction "2_2") (pintype "passive"))
      (node (ref "R9") (pin "2") (pinfunction "2_2") (pintype "passive"))
      (node (ref "U$1") (pin "GND.1") (pinfunction "GND.1_GND.1") (pintype "bidirectional"))
      (node (ref "U$1") (pin "GND.2") (pinfunction "GND.2_GND.2") (pintype "bidirectional"))
      (node (ref "U$2") (pin "GND") (pinfunction "P$3_GND") (pintype "bidirectional"))
    )
    (net (code "66") (name "Net-(DIS1-CONTR)") (class "Default")
      (node (ref "DIS1") (pin "3") (pinfunction "CONTR_3") (pintype "input"))
      (node (ref "R45") (pin "2") (pinfunction "2_2") (pintype "passive"))
    )
    (net (code "67") (name "Net-(DIS1-LED+)") (class "Default")
      (node (ref "DIS1") (pin "15") (pinfunction "LED+_15") (pintype "passive"))
      (node (ref "R1") (pin "2") (pinfunction "2_2") (pintype "passive"))
    )
    (net (code "68") (name "Net-(JP2-Pad35)") (class "Default")
      (node (ref "JP2") (pin "35") (pinfunction "35_35") (pintype "passive"))
      (node (ref "R39") (pin "2") (pinfunction "2_2") (pintype "passive"))
    )
    (net (code "69") (name "Net-(JP2-Pad37)") (class "Default")
      (node (ref "JP2") (pin "37") (pinfunction "37_37") (pintype "passive"))
      (node (ref "R38") (pin "2") (pinfunction "2_2") (pintype "passive"))
    )
    (net (code "70") (name "Net-(LED1-PadA)") (class "Default")
      (node (ref "LED1") (pin "A") (pinfunction "A_A") (pintype "passive"))
      (node (ref "R38") (pin "1") (pinfunction "1_1") (pintype "passive"))
    )
    (net (code "71") (name "Net-(LED2-PadA)") (class "Default")
      (node (ref "LED2") (pin "A") (pinfunction "A_A") (pintype "passive"))
      (node (ref "R39") (pin "1") (pinfunction "1_1") (pintype "passive"))
    )
    (net (code "72") (name "Net-(LED3-PadA)") (class "Default")
      (node (ref "LED3") (pin "A") (pinfunction "A_A") (pintype "passive"))
      (node (ref "R40") (pin "1") (pinfunction "1_1") (pintype "passive"))
    )
    (net (code "73") (name "Net-(LED4-PadA)") (class "Default")
      (node (ref "LED4") (pin "A") (pinfunction "A_A") (pintype "passive"))
      (node (ref "R41") (pin "1") (pinfunction "1_1") (pintype "passive"))
    )
    (net (code "74") (name "Net-(LED5-PadA)") (class "Default")
      (node (ref "LED5") (pin "A") (pinfunction "A_A") (pintype "passive"))
      (node (ref "R42") (pin "1") (pinfunction "1_1") (pintype "passive"))
    )
    (net (code "75") (name "Net-(LED6-PadA)") (class "Default")
      (node (ref "LED6") (pin "A") (pinfunction "A_A") (pintype "passive"))
      (node (ref "R43") (pin "1") (pinfunction "1_1") (pintype "passive"))
    )
    (net (code "76") (name "Net-(R41-Pad2)") (class "Default")
      (node (ref "R41") (pin "2") (pinfunction "2_2") (pintype "passive"))
      (node (ref "U$1") (pin "D10") (pinfunction "D10_D10") (pintype "bidirectional"))
    )
    (net (code "77") (name "Net-(R42-Pad2)") (class "Default")
      (node (ref "R42") (pin "2") (pinfunction "2_2") (pintype "passive"))
      (node (ref "U$1") (pin "D11") (pinfunction "D11_D11") (pintype "bidirectional"))
    )
    (net (code "78") (name "Net-(R43-Pad2)") (class "Default")
      (node (ref "R43") (pin "2") (pinfunction "2_2") (pintype "passive"))
      (node (ref "U$1") (pin "D12") (pinfunction "D12_D12") (pintype "bidirectional"))
    )
    (net (code "79") (name "unconnected-(DIS1-DB0-Pad7)") (class "Default")
      (node (ref "DIS1") (pin "7") (pinfunction "DB0_7") (pintype "bidirectional"))
    )
    (net (code "80") (name "unconnected-(DIS1-DB1-Pad8)") (class "Default")
      (node (ref "DIS1") (pin "8") (pinfunction "DB1_8") (pintype "bidirectional"))
    )
    (net (code "81") (name "unconnected-(DIS1-DB2-Pad9)") (class "Default")
      (node (ref "DIS1") (pin "9") (pinfunction "DB2_9") (pintype "bidirectional"))
    )
    (net (code "82") (name "unconnected-(DIS1-DB3-Pad10)") (class "Default")
      (node (ref "DIS1") (pin "10") (pinfunction "DB3_10") (pintype "bidirectional"))
    )
    (net (code "83") (name "unconnected-(JP2-Pad2)") (class "Default")
      (node (ref "JP2") (pin "2") (pinfunction "2_2") (pintype "passive"))
    )
    (net (code "84") (name "unconnected-(JP2-Pad3)") (class "Default")
      (node (ref "JP2") (pin "3") (pinfunction "3_3") (pintype "passive"))
    )
    (net (code "85") (name "unconnected-(JP2-Pad5)") (class "Default")
      (node (ref "JP2") (pin "5") (pinfunction "5_5") (pintype "passive"))
    )
    (net (code "86") (name "unconnected-(JP2-Pad7)") (class "Default")
      (node (ref "JP2") (pin "7") (pinfunction "7_7") (pintype "passive"))
    )
    (net (code "87") (name "unconnected-(JP2-Pad9)") (class "Default")
      (node (ref "JP2") (pin "9") (pinfunction "9_9") (pintype "passive"))
    )
    (net (code "88") (name "unconnected-(JP2-Pad11)") (class "Default")
      (node (ref "JP2") (pin "11") (pinfunction "11_11") (pintype "passive"))
    )
    (net (code "89") (name "unconnected-(JP2-Pad13)") (class "Default")
      (node (ref "JP2") (pin "13") (pinfunction "13_13") (pintype "passive"))
    )
    (net (code "90") (name "unconnected-(JP2-Pad17)") (class "Default")
      (node (ref "JP2") (pin "17") (pinfunction "17_17") (pintype "passive"))
    )
    (net (code "91") (name "unconnected-(JP2-Pad19)") (class "Default")
      (node (ref "JP2") (pin "19") (pinfunction "19_19") (pintype "passive"))
    )
    (net (code "92") (name "unconnected-(JP2-Pad21)") (class "Default")
      (node (ref "JP2") (pin "21") (pinfunction "21_21") (pintype "passive"))
    )
    (net (code "93") (name "unconnected-(JP2-Pad25)") (class "Default")
      (node (ref "JP2") (pin "25") (pinfunction "25_25") (pintype "passive"))
    )
    (net (code "94") (name "unconnected-(JP2-Pad27)") (class "Default")
      (node (ref "JP2") (pin "27") (pinfunction "27_27") (pintype "passive"))
    )
    (net (code "95") (name "unconnected-(JP2-Pad29)") (class "Default")
      (node (ref "JP2") (pin "29") (pinfunction "29_29") (pintype "passive"))
    )
    (net (code "96") (name "unconnected-(JP2-Pad33)") (class "Default")
      (node (ref "JP2") (pin "33") (pinfunction "33_33") (pintype "passive"))
    )
    (net (code "97") (name "unconnected-(JP4-Pad1)") (class "Default")
      (node (ref "JP4") (pin "1") (pinfunction "1_1") (pintype "passive"))
    )
    (net (code "98") (name "unconnected-(JP4-Pad6)") (class "Default")
      (node (ref "JP4") (pin "6") (pinfunction "6_6") (pintype "passive"))
    )
    (net (code "99") (name "unconnected-(U$1-+3V3.1-Pad3V3.1)") (class "Default")
      (node (ref "U$1") (pin "3V3.1") (pinfunction "+3V3.1_3V3.1") (pintype "bidirectional"))
    )
    (net (code "100") (name "unconnected-(U$1-+3V3.2-Pad3V3.2)") (class "Default")
      (node (ref "U$1") (pin "3V3.2") (pinfunction "+3V3.2_3V3.2") (pintype "bidirectional"))
    )
    (net (code "101") (name "unconnected-(U$1-AREF-PadAREF.1)") (class "Default")
      (node (ref "U$1") (pin "AREF.1") (pinfunction "AREF_AREF.1") (pintype "bidirectional"))
    )
    (net (code "102") (name "unconnected-(U$1-PadA0)") (class "Default")
      (node (ref "U$1") (pin "A0") (pinfunction "A0_A0") (pintype "bidirectional"))
    )
    (net (code "103") (name "unconnected-(U$1-PadA1)") (class "Default")
      (node (ref "U$1") (pin "A1") (pinfunction "A1_A1") (pintype "bidirectional"))
    )
    (net (code "104") (name "unconnected-(U$1-PadA2)") (class "Default")
      (node (ref "U$1") (pin "A2") (pinfunction "A2_A2") (pintype "bidirectional"))
    )
    (net (code "105") (name "unconnected-(U$1-PadA3)") (class "Default")
      (node (ref "U$1") (pin "A3") (pinfunction "A3_A3") (pintype "bidirectional"))
    )
    (net (code "106") (name "unconnected-(U$1-PadA4)") (class "Default")
      (node (ref "U$1") (pin "A4") (pinfunction "A4_A4") (pintype "bidirectional"))
    )
    (net (code "107") (name "unconnected-(U$1-PadA5)") (class "Default")
      (node (ref "U$1") (pin "A5") (pinfunction "A5_A5") (pintype "bidirectional"))
    )
    (net (code "108") (name "unconnected-(U$1-PadA6)") (class "Default")
      (node (ref "U$1") (pin "A6") (pinfunction "A6_A6") (pintype "bidirectional"))
    )
    (net (code "109") (name "unconnected-(U$1-PadA7)") (class "Default")
      (node (ref "U$1") (pin "A7") (pinfunction "A7_A7") (pintype "bidirectional"))
    )
    (net (code "110") (name "unconnected-(U$1-PadA8)") (class "Default")
      (node (ref "U$1") (pin "A8") (pinfunction "A8_A8") (pintype "bidirectional"))
    )
    (net (code "111") (name "unconnected-(U$1-PadA9)") (class "Default")
      (node (ref "U$1") (pin "A9") (pinfunction "A9_A9") (pintype "bidirectional"))
    )
    (net (code "112") (name "unconnected-(U$1-PadA10)") (class "Default")
      (node (ref "U$1") (pin "A10") (pinfunction "A10_A10") (pintype "bidirectional"))
    )
    (net (code "113") (name "unconnected-(U$1-PadA11)") (class "Default")
      (node (ref "U$1") (pin "A11") (pinfunction "A11_A11") (pintype "bidirectional"))
    )
    (net (code "114") (name "unconnected-(U$1-PadA12)") (class "Default")
      (node (ref "U$1") (pin "A12") (pinfunction "A12_A12") (pintype "bidirectional"))
    )
    (net (code "115") (name "unconnected-(U$1-PadA13)") (class "Default")
      (node (ref "U$1") (pin "A13") (pinfunction "A13_A13") (pintype "bidirectional"))
    )
    (net (code "116") (name "unconnected-(U$1-PadD13)") (class "Default")
      (node (ref "U$1") (pin "D13") (pinfunction "D13_D13") (pintype "bidirectional"))
    )
    (net (code "117") (name "unconnected-(U$1-PadD18)") (class "Default")
      (node (ref "U$1") (pin "D18") (pinfunction "D18_D18") (pintype "bidirectional"))
    )
    (net (code "118") (name "unconnected-(U$1-PadD19)") (class "Default")
      (node (ref "U$1") (pin "D19") (pinfunction "D19_D19") (pintype "bidirectional"))
    )
    (net (code "119") (name "unconnected-(U$1-PadRST)") (class "Default")
      (node (ref "U$1") (pin "RST") (pinfunction "RST_RST") (pintype "bidirectional"))
    )
    (net (code "120") (name "unconnected-(U$1-PadRX)") (class "Default")
      (node (ref "U$1") (pin "RX") (pinfunction "RX_RX") (pintype "bidirectional"))
    )
    (net (code "121") (name "unconnected-(U$1-PadTX)") (class "Default")
      (node (ref "U$1") (pin "TX") (pinfunction "TX_TX") (pintype "bidirectional"))
    )
    (net (code "122") (name "unconnected-(U$1-PadVIN.1)") (class "Default")
      (node (ref "U$1") (pin "VIN.1") (pinfunction "VIN.1_VIN.1") (pintype "bidirectional"))
    )
    (net (code "123") (name "unconnected-(U$1-PadVIN.2)") (class "Default")
      (node (ref "U$1") (pin "VIN.2") (pinfunction "VIN.2_VIN.2") (pintype "bidirectional"))
    )
    (net (code "124") (name "unconnected-(U$2-P$1-Pad3V0)") (class "Default")
      (node (ref "U$2") (pin "3V0") (pinfunction "P$1_3V0") (pintype "bidirectional"))
    )
    (net (code "125") (name "unconnected-(U$2-P$2-PadADR)") (class "Default")
      (node (ref "U$2") (pin "ADR") (pinfunction "P$2_ADR") (pintype "bidirectional"))
    )
    (net (code "126") (name "unconnected-(U$2-P$4-PadINT)") (class "Default")
      (node (ref "U$2") (pin "INT") (pinfunction "P$4_INT") (pintype "bidirectional"))
    )
    (net (code "127") (name "unconnected-(U$2-P$5-PadPS0)") (class "Default")
      (node (ref "U$2") (pin "PS0") (pinfunction "P$5_PS0") (pintype "bidirectional"))
    )
    (net (code "128") (name "unconnected-(U$2-P$6-PadPS1)") (class "Default")
      (node (ref "U$2") (pin "PS1") (pinfunction "P$6_PS1") (pintype "bidirectional"))
    )
    (net (code "129") (name "unconnected-(U$2-P$7-PadRST)") (class "Default")
      (node (ref "U$2") (pin "RST") (pinfunction "P$7_RST") (pintype "bidirectional"))
    )
  )
)
